# HVSUP_ISOL.net
KiCad netlist of a schematic drawn in Altium Designer
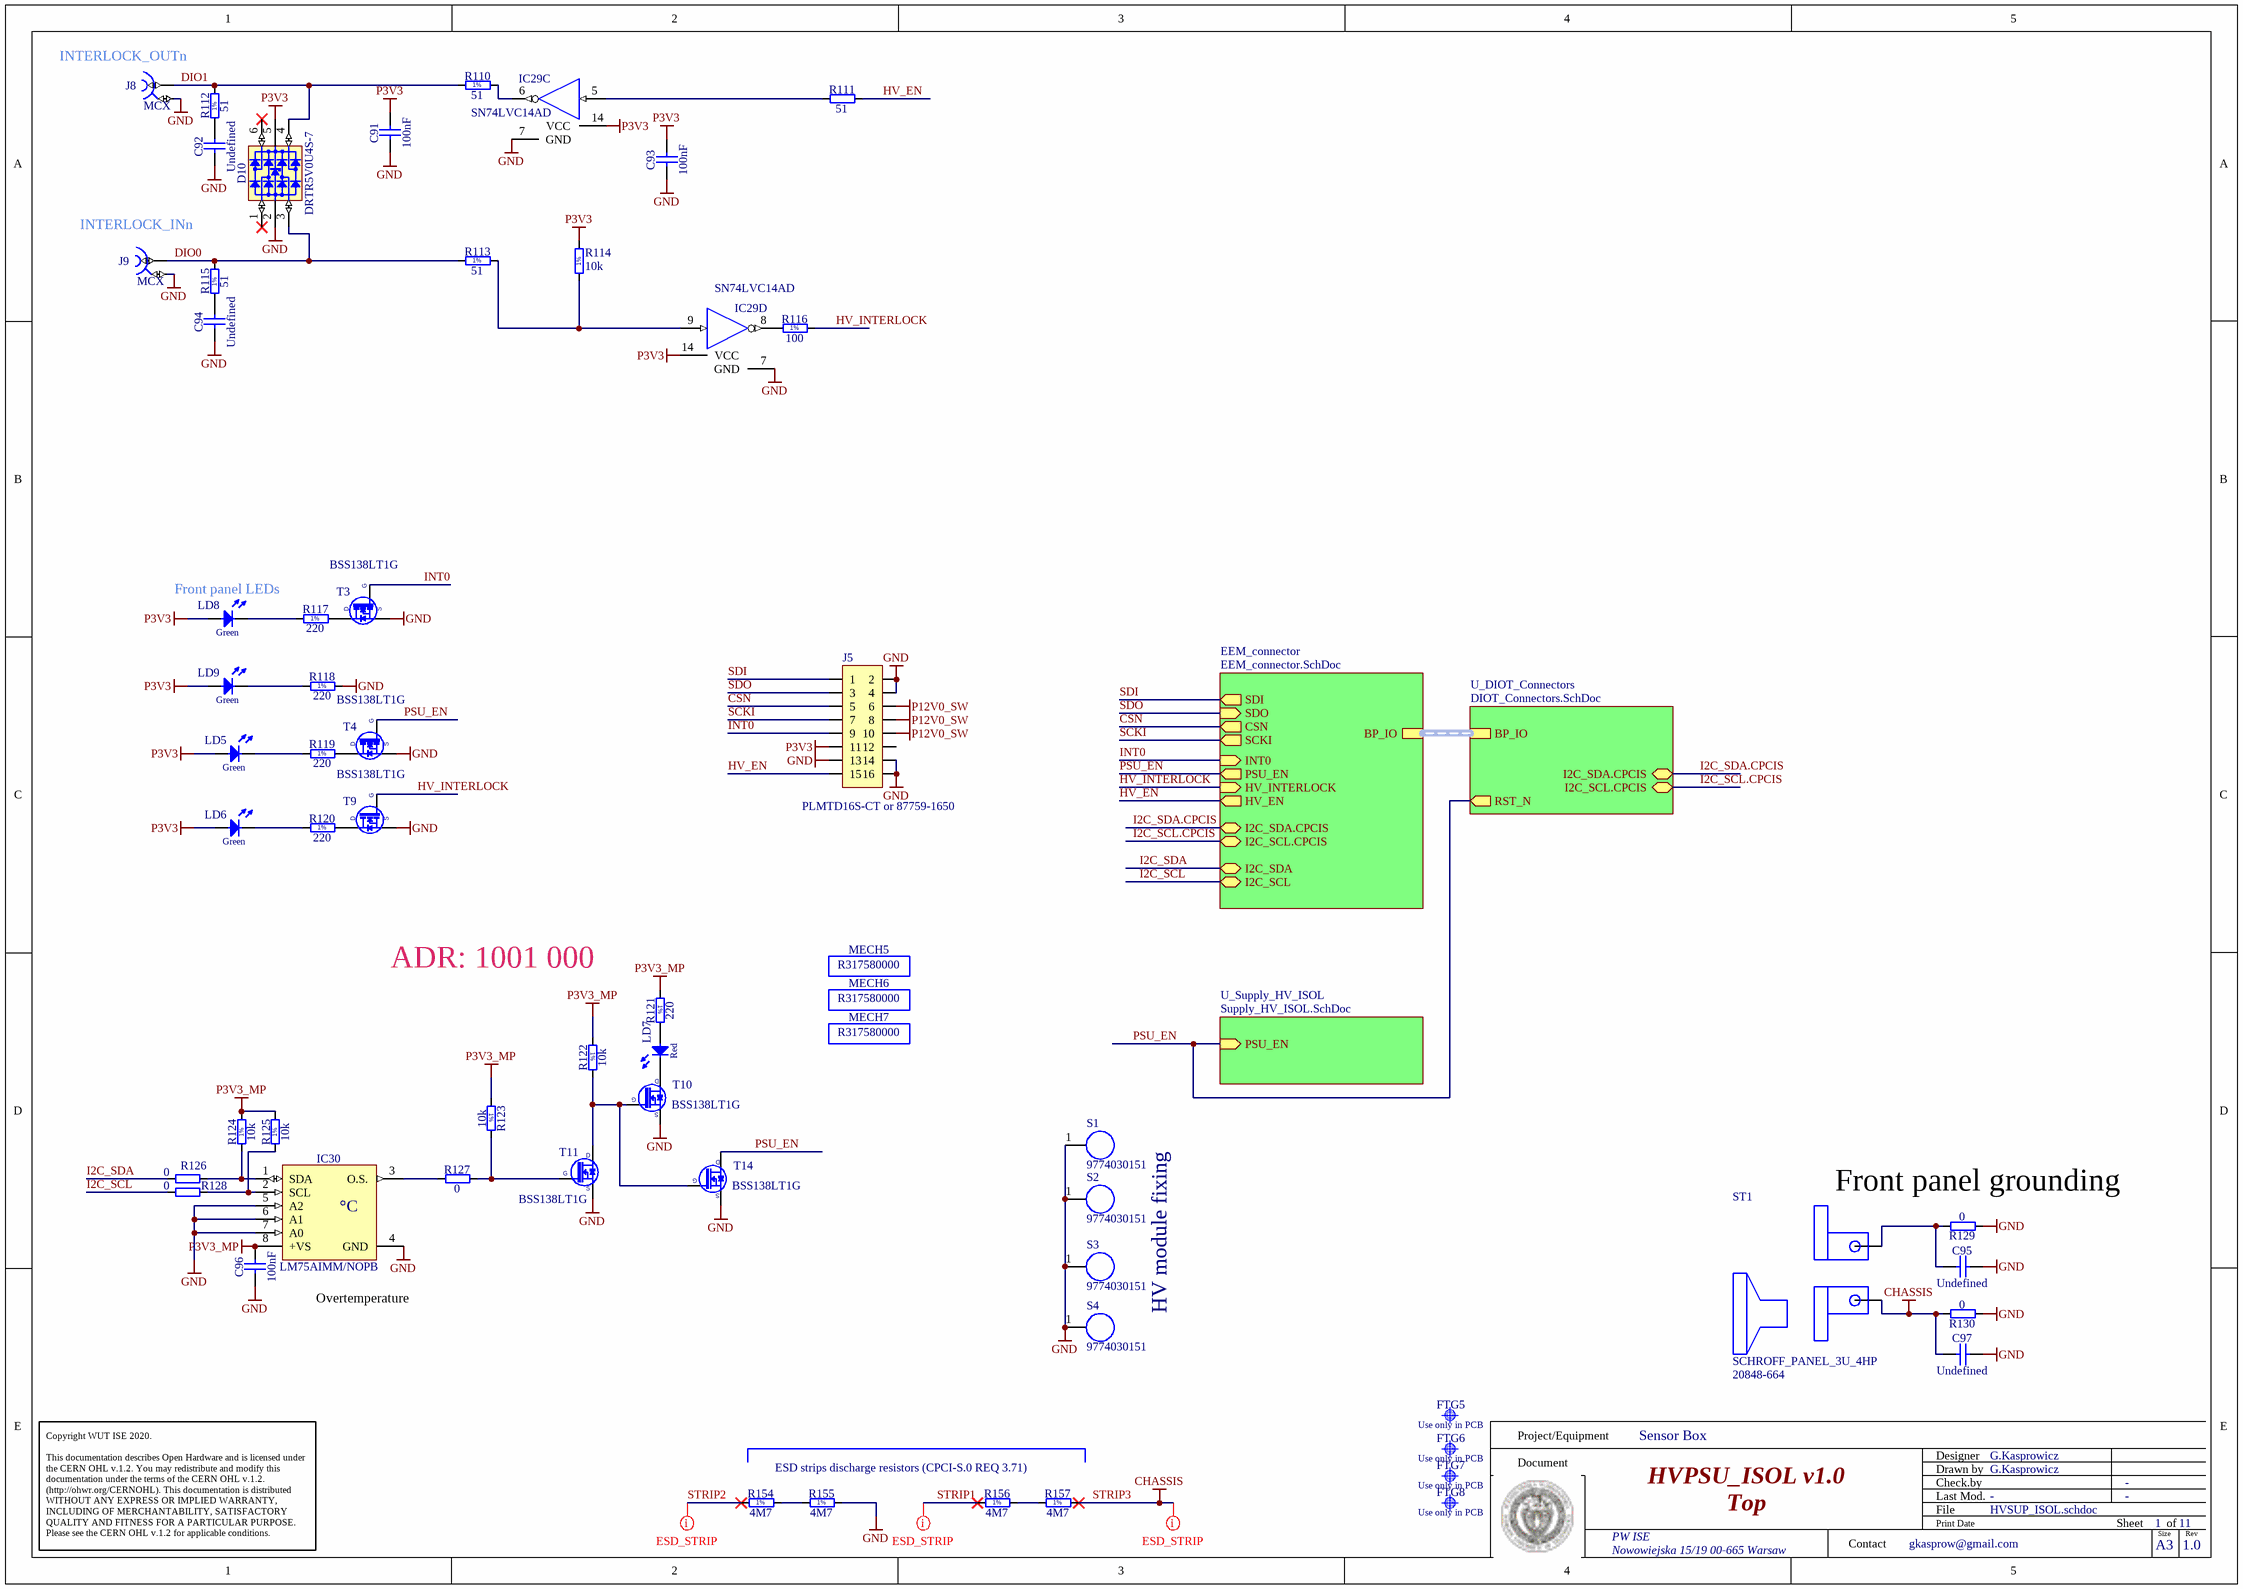
[diagram p0: HVSUP_ISOL.schdoc]

(export (version "E")
  (design (tool "Eeschema 10.0.6"))
  (components
    (comp (ref "C91")
      (value "100nF")
      (footprint "CAPC1005X55N")
      (description "Non-polarised capacitor")
      (fields
        (field (name "PART NUMBER") "CC0402_100NF_16V_10%_X7R")
        (field (name "VOLTAGE") "16V")
        (field (name "AUTHOR") "CERN DEM JLC")
      )
      (libsource (lib "Capacitors") (part "Capacitor - non polarized"))
    )
    (comp (ref "C92")
      (value "Undefined")
      (footprint "CAPC1608X90N")
      (description "Non-polarised capacitor")
      (fields (field (name "PART NUMBER") "CC0603_NO-VALUE") (field (name "AUTHOR") "CERN DEM MR"))
      (libsource (lib "Capacitors") (part "Capacitor - non polarized"))
    )
    (comp (ref "C93")
      (value "100nF")
      (footprint "CAPC1005X55N")
      (description "Non-polarised capacitor")
      (fields
        (field (name "PART NUMBER") "CC0402_100NF_16V_10%_X7R")
        (field (name "VOLTAGE") "16V")
        (field (name "AUTHOR") "CERN DEM JLC")
      )
      (libsource (lib "Capacitors") (part "Capacitor - non polarized"))
    )
    (comp (ref "C94")
      (value "Undefined")
      (footprint "CAPC1608X90N")
      (description "Non-polarised capacitor")
      (fields (field (name "PART NUMBER") "CC0603_NO-VALUE") (field (name "AUTHOR") "CERN DEM MR"))
      (libsource (lib "Capacitors") (part "Capacitor - non polarized"))
    )
    (comp (ref "C95")
      (value "Undefined")
      (footprint "CAPC2012X135N")
      (description "Non-polarised capacitor")
      (fields (field (name "PART NUMBER") "CC0805_NO-VALUE") (field (name "AUTHOR") "CERN DEM JLC"))
      (libsource (lib "Capacitors") (part "Capacitor - non polarized"))
    )
    (comp (ref "C96")
      (value "100nF")
      (footprint "CAPC1005X55N")
      (description "Non-polarised capacitor")
      (fields
        (field (name "PART NUMBER") "CC0402_100NF_16V_10%_X5R")
        (field (name "VOLTAGE") "16V")
        (field (name "AUTHOR") "CERN DEM JLC")
      )
      (libsource (lib "Capacitors") (part "Capacitor - non polarized"))
    )
    (comp (ref "C97")
      (value "Undefined")
      (footprint "CAPC2012X135N")
      (description "Non-polarised capacitor")
      (fields (field (name "PART NUMBER") "CC0805_NO-VALUE") (field (name "AUTHOR") "CERN DEM JLC"))
      (libsource (lib "Capacitors") (part "Capacitor - non polarized"))
    )
    (comp (ref "D10")
      (value "DRTR5V0U4S-7")
      (footprint "SOT65P210X110-6N")
      (description "Integrated Quad Ultra-Low Capacitance ESD Protection")
      (fields (field (name "MANUFACTURER") "DIODES") (field (name "AUTHOR") "GK"))
      (libsource (lib "Diodes") (part "D_TVS_DRTR5V0U4S-7"))
    )
    (comp (ref "FTG5")
      (value "Use only in PCB")
      (footprint "FIDUCIAL_TOP_C100-200")
      (description "Fiducial Target")
      (fields (field (name "PART NUMBER") "FIDUCIAL_TARGET_C100-200") (field (name "AUTHOR") "CERN DEM JLC"))
      (libsource (lib "Eletro-mechanical") (part "Fiducial Target"))
    )
    (comp (ref "FTG6")
      (value "Use only in PCB")
      (footprint "FIDUCIAL_TOP_S100-200")
      (description "Fiducial Target")
      (fields (field (name "PART NUMBER") "FIDUCIAL_TARGET_S100-200") (field (name "AUTHOR") "CERN DEM JLC"))
      (libsource (lib "Eletro-mechanical") (part "Fiducial Target"))
    )
    (comp (ref "FTG7")
      (value "Use only in PCB")
      (footprint "FIDUCIAL_TOP_S100-200")
      (description "Fiducial Target")
      (fields (field (name "PART NUMBER") "FIDUCIAL_TARGET_S100-200") (field (name "AUTHOR") "CERN DEM JLC"))
      (libsource (lib "Eletro-mechanical") (part "Fiducial Target"))
    )
    (comp (ref "FTG8")
      (value "Use only in PCB")
      (footprint "FIDUCIAL_TOP_S100-200")
      (description "Fiducial Target")
      (fields (field (name "PART NUMBER") "FIDUCIAL_TARGET_S100-200") (field (name "AUTHOR") "CERN DEM JLC"))
      (libsource (lib "Eletro-mechanical") (part "Fiducial Target"))
    )
    (comp (ref "IC29")
      (value "SN74LVC14AD")
      (footprint "SOIC127P600X175-14N")
      (description "Hex Schmitt-Trigger Inverter")
      (fields (field (name "MANUFACTURER") "TEXAS INSTRUMENTS") (field (name "AUTHOR") "CERN DEM JMW"))
      (libsource (lib "ICs And Semiconductors") (part "7414"))
    )
    (comp (ref "IC30")
      (value "LM75AIMM/NOPB")
      (footprint "SOP65P490X109-8N")
      (description "Digital Temperature Sensor and Thermal Watchdog with Two-Wire Interface")
      (fields (field (name "MANUFACTURER") "TEXAS INSTRUMENTS") (field (name "AUTHOR") "CERN DEM JLC"))
      (libsource (lib "ICs And Semiconductors") (part "LM75"))
    )
    (comp (ref "J5")
      (value "PLMTD16S-CT or 87759-1650")
      (footprint "87759-1650")
      (description "2mm  dual row rheader (Maritex)")
      (fields (field (name "MANUFACTURER") "Molex") (field (name "MANUFACTURER PART NUMBER") "87759-1650"))
      (libsource (lib "LIBRARY_SCH") (part "CON_2x8 2mm male"))
    )
    (comp (ref "J8")
      (value "MCX")
      (footprint "AMPHENOL_919-383J-51A")
      (fields
        (field (name "PART NUMBER") "AMPHENOL_919-383J-51A")
        (field (name "MANUFACTURER") "AMPHENOL")
        (field (name "MANUFACTURER PART NUMBER") "919-383J-51A")
        (field (name "AUTHOR") "CERN DEM BC")
      )
      (libsource (lib "Connectors") (part "Coax_1Female_1Shield"))
    )
    (comp (ref "J9")
      (value "MCX")
      (footprint "AMPHENOL_919-383J-51A")
      (fields
        (field (name "PART NUMBER") "AMPHENOL_919-383J-51A")
        (field (name "MANUFACTURER") "AMPHENOL")
        (field (name "MANUFACTURER PART NUMBER") "919-383J-51A")
        (field (name "AUTHOR") "CERN DEM BC")
      )
      (libsource (lib "Connectors") (part "Coax_1Female_1Shield"))
    )
    (comp (ref "LD5")
      (value "Green")
      (footprint "LED_DIALIGHT_555-230")
      (description "LED Green 1C 2A")
      (fields
        (field (name "PART NUMBER") "LED_DIALIGHT_555-2301F")
        (field (name "MANUFACTURER") "DIALIGHT")
        (field (name "AUTHOR") "CERN DEM JMW")
      )
      (libsource (lib "ICs And Semiconductors") (part "LED Green 1C 2A"))
    )
    (comp (ref "LD6")
      (value "Green")
      (footprint "LED_DIALIGHT_555-230")
      (description "LED Green 1C 2A")
      (fields
        (field (name "PART NUMBER") "LED_DIALIGHT_555-2301F")
        (field (name "MANUFACTURER") "DIALIGHT")
        (field (name "AUTHOR") "CERN DEM JMW")
      )
      (libsource (lib "ICs And Semiconductors") (part "LED Green 1C 2A"))
    )
    (comp (ref "LD7")
      (value "Red")
      (footprint "LED_DIALIGHT_555-200")
      (description "LED Red 1C 2A")
      (fields
        (field (name "PART NUMBER") "LED_DIALIGHT_555-2001F")
        (field (name "MANUFACTURER") "DIALIGHT")
        (field (name "AUTHOR") "CERN DEM JMW")
      )
      (libsource (lib "ICs And Semiconductors") (part "LED Red 1C 2A"))
    )
    (comp (ref "LD8")
      (value "Green")
      (footprint "LED_DIALIGHT_555-230")
      (description "LED Green 1C 2A")
      (fields
        (field (name "PART NUMBER") "LED_DIALIGHT_555-2301F")
        (field (name "MANUFACTURER") "DIALIGHT")
        (field (name "AUTHOR") "CERN DEM JMW")
      )
      (libsource (lib "ICs And Semiconductors") (part "LED Green 1C 2A"))
    )
    (comp (ref "LD9")
      (value "Green")
      (footprint "LED_DIALIGHT_555-230")
      (description "LED Green 1C 2A")
      (fields
        (field (name "PART NUMBER") "LED_DIALIGHT_555-2301F")
        (field (name "MANUFACTURER") "DIALIGHT")
        (field (name "AUTHOR") "CERN DEM JMW")
      )
      (libsource (lib "ICs And Semiconductors") (part "LED Green 1C 2A"))
    )
    (comp (ref "MECH5")
      (value "R317580000")
      (footprint "GENERIC_MECH")
      (description "SHV connector")
      (fields (field (name "MANUFACTURER") "Radiall") (field (name "AUTHOR") "GK"))
      (libsource (lib "Mechanical") (part "Generic_mechanical"))
    )
    (comp (ref "MECH6")
      (value "R317580000")
      (footprint "GENERIC_MECH")
      (description "SHV connector")
      (fields (field (name "MANUFACTURER") "Radiall") (field (name "AUTHOR") "GK"))
      (libsource (lib "Mechanical") (part "Generic_mechanical"))
    )
    (comp (ref "MECH7")
      (value "R317580000")
      (footprint "GENERIC_MECH")
      (description "SHV connector")
      (fields (field (name "MANUFACTURER") "Radiall") (field (name "AUTHOR") "GK"))
      (libsource (lib "Mechanical") (part "Generic_mechanical"))
    )
    (comp (ref "R110")
      (value "51")
      (footprint "RESC1005X40N")
      (description "Resistor - 1%")
      (fields
        (field (name "PART NUMBER") "R0402_51R_1%_0.0625W_100PPM")
        (field (name "POWER") "0.0625W")
        (field (name "AUTHOR") "CERN DEM JLC")
      )
      (libsource (lib "Resistors") (part "Resistor - 1%"))
    )
    (comp (ref "R111")
      (value "51")
      (footprint "RESC1005X40N")
      (description "Resistor - 1%")
      (fields
        (field (name "PART NUMBER") "R0402_51R_1%_0.0625W_100PPM")
        (field (name "POWER") "0.0625W")
        (field (name "AUTHOR") "CERN DEM JLC")
      )
      (libsource (lib "Resistors") (part "Resistor - 1%"))
    )
    (comp (ref "R112")
      (value "51")
      (footprint "RESC1005X40N")
      (description "Resistor - 1%")
      (fields
        (field (name "PART NUMBER") "R0402_51R_1%_0.0625W_100PPM")
        (field (name "POWER") "0.0625W")
        (field (name "AUTHOR") "CERN DEM JLC")
      )
      (libsource (lib "Resistors") (part "Resistor - 1%"))
    )
    (comp (ref "R113")
      (value "51")
      (footprint "RESC1005X40N")
      (description "Resistor - 1%")
      (fields
        (field (name "PART NUMBER") "R0402_51R_1%_0.0625W_100PPM")
        (field (name "POWER") "0.0625W")
        (field (name "AUTHOR") "CERN DEM JLC")
      )
      (libsource (lib "Resistors") (part "Resistor - 1%"))
    )
    (comp (ref "R114")
      (value "10k")
      (footprint "RESC1005X40N")
      (description "Resistor - 1%")
      (fields
        (field (name "PART NUMBER") "R0402_10K_1%_0.0625W_100PPM")
        (field (name "POWER") "0.0625W")
        (field (name "AUTHOR") "CERN DEM JLC")
      )
      (libsource (lib "Resistors") (part "Resistor - 1%"))
    )
    (comp (ref "R115")
      (value "51")
      (footprint "RESC1005X40N")
      (description "Resistor - 1%")
      (fields
        (field (name "PART NUMBER") "R0402_51R_1%_0.0625W_100PPM")
        (field (name "POWER") "0.0625W")
        (field (name "AUTHOR") "CERN DEM JLC")
      )
      (libsource (lib "Resistors") (part "Resistor - 1%"))
    )
    (comp (ref "R116")
      (value "100")
      (footprint "RESC1005X40N")
      (description "Resistor - 1%")
      (fields
        (field (name "PART NUMBER") "R0402_100R_1%_0.0625W_100PPM")
        (field (name "POWER") "0.0625W")
        (field (name "AUTHOR") "CERN DEM JLC")
      )
      (libsource (lib "Resistors") (part "Resistor - 1%"))
    )
    (comp (ref "R117")
      (value "220")
      (footprint "RESC1608X55N")
      (description "Resistor - 1%")
      (fields
        (field (name "PART NUMBER") "R0603_220R_1%_0.1W_100PPM")
        (field (name "POWER") "0.1W")
        (field (name "AUTHOR") "CERN DEM JLC")
      )
      (libsource (lib "Resistors") (part "Resistor - 1%"))
    )
    (comp (ref "R118")
      (value "220")
      (footprint "RESC1608X55N")
      (description "Resistor - 1%")
      (fields
        (field (name "PART NUMBER") "R0603_220R_1%_0.1W_100PPM")
        (field (name "POWER") "0.1W")
        (field (name "AUTHOR") "CERN DEM JLC")
      )
      (libsource (lib "Resistors") (part "Resistor - 1%"))
    )
    (comp (ref "R119")
      (value "220")
      (footprint "RESC1608X55N")
      (description "Resistor - 1%")
      (fields
        (field (name "PART NUMBER") "R0603_220R_1%_0.1W_100PPM")
        (field (name "POWER") "0.1W")
        (field (name "AUTHOR") "CERN DEM JLC")
      )
      (libsource (lib "Resistors") (part "Resistor - 1%"))
    )
    (comp (ref "R120")
      (value "220")
      (footprint "RESC1608X55N")
      (description "Resistor - 1%")
      (fields
        (field (name "PART NUMBER") "R0603_220R_1%_0.1W_100PPM")
        (field (name "POWER") "0.1W")
        (field (name "AUTHOR") "CERN DEM JLC")
      )
      (libsource (lib "Resistors") (part "Resistor - 1%"))
    )
    (comp (ref "R121")
      (value "220")
      (footprint "RESC1608X55N")
      (description "Resistor - 1%")
      (fields
        (field (name "PART NUMBER") "R0603_220R_1%_0.1W_100PPM")
        (field (name "POWER") "0.1W")
        (field (name "AUTHOR") "CERN DEM JLC")
      )
      (libsource (lib "Resistors") (part "Resistor - 1%"))
    )
    (comp (ref "R122")
      (value "10k")
      (footprint "RESC1005X40N")
      (description "Resistor - 1%")
      (fields
        (field (name "PART NUMBER") "R0402_10K_1%_0.0625W_100PPM")
        (field (name "POWER") "0.0625W")
        (field (name "AUTHOR") "CERN DEM JLC")
      )
      (libsource (lib "Resistors") (part "Resistor - 1%"))
    )
    (comp (ref "R123")
      (value "10k")
      (footprint "RESC1005X40N")
      (description "Resistor - 1%")
      (fields
        (field (name "PART NUMBER") "R0402_10K_1%_0.0625W_100PPM")
        (field (name "POWER") "0.0625W")
        (field (name "AUTHOR") "CERN DEM JLC")
      )
      (libsource (lib "Resistors") (part "Resistor - 1%"))
    )
    (comp (ref "R124")
      (value "10k")
      (footprint "RESC1005X40N")
      (description "Resistor - 1%")
      (fields
        (field (name "PART NUMBER") "R0402_10K_1%_0.0625W_100PPM")
        (field (name "POWER") "0.0625W")
        (field (name "AUTHOR") "CERN DEM JLC")
      )
      (libsource (lib "Resistors") (part "Resistor - 1%"))
    )
    (comp (ref "R125")
      (value "10k")
      (footprint "RESC1005X40N")
      (description "Resistor - 1%")
      (fields
        (field (name "PART NUMBER") "R0402_10K_1%_0.0625W_100PPM")
        (field (name "POWER") "0.0625W")
        (field (name "AUTHOR") "CERN DEM JLC")
      )
      (libsource (lib "Resistors") (part "Resistor - 1%"))
    )
    (comp (ref "R126")
      (value "0")
      (footprint "RESC1005X40N")
      (description "Resistor")
      (fields
        (field (name "PART NUMBER") "R0402_0R_JUMPER")
        (field (name "MANUFACTURER") "GENERIC")
        (field (name "AUTHOR") "CERN DEM JLC")
      )
      (libsource (lib "Resistors") (part "Resistor"))
    )
    (comp (ref "R127")
      (value "0")
      (footprint "RESC1005X40N")
      (description "Resistor")
      (fields
        (field (name "PART NUMBER") "R0402_0R_JUMPER")
        (field (name "MANUFACTURER") "GENERIC")
        (field (name "AUTHOR") "CERN DEM JLC")
      )
      (libsource (lib "Resistors") (part "Resistor"))
    )
    (comp (ref "R128")
      (value "0")
      (footprint "RESC1005X40N")
      (description "Resistor")
      (fields
        (field (name "PART NUMBER") "R0402_0R_JUMPER")
        (field (name "MANUFACTURER") "GENERIC")
        (field (name "AUTHOR") "CERN DEM JLC")
      )
      (libsource (lib "Resistors") (part "Resistor"))
    )
    (comp (ref "R129")
      (value "0")
      (footprint "RESC1608X55N")
      (description "Resistor")
      (fields
        (field (name "PART NUMBER") "R0603_0R_JUMPER")
        (field (name "MANUFACTURER") "GENERIC")
        (field (name "AUTHOR") "CERN DEM JLC")
      )
      (libsource (lib "Resistors") (part "Resistor"))
    )
    (comp (ref "R130")
      (value "0")
      (footprint "RESC1608X55N")
      (description "Resistor")
      (fields
        (field (name "PART NUMBER") "R0603_0R_JUMPER")
        (field (name "MANUFACTURER") "GENERIC")
        (field (name "AUTHOR") "CERN DEM JLC")
      )
      (libsource (lib "Resistors") (part "Resistor"))
    )
    (comp (ref "R154")
      (value "4M7")
      (footprint "RESC2113X55N")
      (description "Resistor - 1%")
      (fields
        (field (name "PART NUMBER") "R0805_4M7_1%_0.125W_100PPM_VISHAY_CRCW e3")
        (field (name "POWER") "0.125W")
        (field (name "AUTHOR") "CERN DEM BR")
      )
      (libsource (lib "Resistors") (part "Resistor - 1%"))
    )
    (comp (ref "R155")
      (value "4M7")
      (footprint "RESC2113X55N")
      (description "Resistor - 1%")
      (fields
        (field (name "PART NUMBER") "R0805_4M7_1%_0.125W_100PPM_VISHAY_CRCW e3")
        (field (name "POWER") "0.125W")
        (field (name "AUTHOR") "CERN DEM BR")
      )
      (libsource (lib "Resistors") (part "Resistor - 1%"))
    )
    (comp (ref "R156")
      (value "4M7")
      (footprint "RESC2113X55N")
      (description "Resistor - 1%")
      (fields
        (field (name "PART NUMBER") "R0805_4M7_1%_0.125W_100PPM_VISHAY_CRCW e3")
        (field (name "POWER") "0.125W")
        (field (name "AUTHOR") "CERN DEM BR")
      )
      (libsource (lib "Resistors") (part "Resistor - 1%"))
    )
    (comp (ref "R157")
      (value "4M7")
      (footprint "RESC2113X55N")
      (description "Resistor - 1%")
      (fields
        (field (name "PART NUMBER") "R0805_4M7_1%_0.125W_100PPM_VISHAY_CRCW e3")
        (field (name "POWER") "0.125W")
        (field (name "AUTHOR") "CERN DEM BR")
      )
      (libsource (lib "Resistors") (part "Resistor - 1%"))
    )
    (comp (ref "S1")
      (value "9774030151")
      (footprint "9774030151")
      (description "WA-SMSI SMD Steel Spacer with internal Thread")
      (fields (field (name "MANUFACTURER") "Wurth Elektronik") (field (name "CREATED BY") "Baojun Chen"))
      (libsource (lib "Altium_SMSI_SMT_STEEL_SPACER_M2_5_THREAD_INTERNAL_rev15a") (part "WA-SMSI,  9774030151"))
    )
    (comp (ref "S2")
      (value "9774030151")
      (footprint "9774030151")
      (description "WA-SMSI SMD Steel Spacer with internal Thread")
      (fields (field (name "MANUFACTURER") "Wurth Elektronik") (field (name "CREATED BY") "Baojun Chen"))
      (libsource (lib "Altium_SMSI_SMT_STEEL_SPACER_M2_5_THREAD_INTERNAL_rev15a") (part "WA-SMSI,  9774030151"))
    )
    (comp (ref "S3")
      (value "9774030151")
      (footprint "9774030151")
      (description "WA-SMSI SMD Steel Spacer with internal Thread")
      (fields (field (name "MANUFACTURER") "Wurth Elektronik") (field (name "CREATED BY") "Baojun Chen"))
      (libsource (lib "Altium_SMSI_SMT_STEEL_SPACER_M2_5_THREAD_INTERNAL_rev15a") (part "WA-SMSI,  9774030151"))
    )
    (comp (ref "S4")
      (value "9774030151")
      (footprint "9774030151")
      (description "WA-SMSI SMD Steel Spacer with internal Thread")
      (fields (field (name "MANUFACTURER") "Wurth Elektronik") (field (name "CREATED BY") "Baojun Chen"))
      (libsource (lib "Altium_SMSI_SMT_STEEL_SPACER_M2_5_THREAD_INTERNAL_rev15a") (part "WA-SMSI,  9774030151"))
    )
    (comp (ref "ST1")
      (value "SCHROFF_PANEL_3U_4HP")
      (footprint "SCHROFF_PANEL_3HP_4U")
      (description "Schroff 3HP 4U EUROCARD Panel Kit")
      (fields
        (field (name "MANUFACTURER") "Schroff")
        (field (name "MANUFACTURER PART NUMBER") "20818-017")
        (field (name "MANUFACTURER PART NUMBER 2") "20848-664")
      )
      (libsource (lib "Mechanical") (part "SCHROFF_PANEL_3U_4HP"))
    )
    (comp (ref "T3")
      (value "BSS138LT1G")
      (footprint "SOT95P240X110-3N")
      (description "N-CHANNEL MOSFET WITH DIODE")
      (fields (field (name "MANUFACTURER") "ON SEMICONDUCTOR") (field (name "AUTHOR") "CERN DEM JLC"))
      (libsource (lib "ICs And Semiconductors") (part "N-MOSFET-D 1G 2S 3D"))
    )
    (comp (ref "T4")
      (value "BSS138LT1G")
      (footprint "SOT95P240X110-3N")
      (description "N-CHANNEL MOSFET WITH DIODE")
      (fields (field (name "MANUFACTURER") "ON SEMICONDUCTOR") (field (name "AUTHOR") "CERN DEM JLC"))
      (libsource (lib "ICs And Semiconductors") (part "N-MOSFET-D 1G 2S 3D"))
    )
    (comp (ref "T9")
      (value "BSS138LT1G")
      (footprint "SOT95P240X110-3N")
      (description "N-CHANNEL MOSFET WITH DIODE")
      (fields (field (name "MANUFACTURER") "ON SEMICONDUCTOR") (field (name "AUTHOR") "CERN DEM JLC"))
      (libsource (lib "ICs And Semiconductors") (part "N-MOSFET-D 1G 2S 3D"))
    )
    (comp (ref "T10")
      (value "BSS138LT1G")
      (footprint "SOT95P240X110-3N")
      (description "N-CHANNEL MOSFET WITH DIODE")
      (fields (field (name "MANUFACTURER") "ON SEMICONDUCTOR") (field (name "AUTHOR") "CERN DEM JLC"))
      (libsource (lib "") (part "N-MOSFET-D 1G 2S 3D_1"))
    )
    (comp (ref "T11")
      (value "BSS138LT1G")
      (footprint "SOT95P240X110-3N")
      (description "N-CHANNEL MOSFET WITH DIODE")
      (fields (field (name "MANUFACTURER") "ON SEMICONDUCTOR") (field (name "AUTHOR") "CERN DEM JLC"))
      (libsource (lib "") (part "N-MOSFET-D 1G 2S 3D_2"))
    )
    (comp (ref "T14")
      (value "BSS138LT1G")
      (footprint "SOT95P240X110-3N")
      (description "N-CHANNEL MOSFET WITH DIODE")
      (fields (field (name "MANUFACTURER") "ON SEMICONDUCTOR") (field (name "AUTHOR") "CERN DEM JLC"))
      (libsource (lib "") (part "N-MOSFET-D 1G 2S 3D_1"))
    )
  )
  (nets
    (net (code "2") (name "/CSN") (class "Default")
      (node (ref "J5") (pin "5") (pinfunction "5_5") (pintype "passive"))
    )
    (net (code "3") (name "/DIO0") (class "Default")
      (node (ref "D10") (pin "3") (pinfunction "I/O2_3") (pintype "bidirectional"))
      (node (ref "J9") (pin "1") (pinfunction "1_1") (pintype "bidirectional"))
      (node (ref "R113") (pin "1") (pinfunction "1_1") (pintype "passive"))
      (node (ref "R115") (pin "2") (pinfunction "2_2") (pintype "passive"))
    )
    (net (code "4") (name "/DIO1") (class "Default")
      (node (ref "D10") (pin "4") (pinfunction "I/O3_4") (pintype "bidirectional"))
      (node (ref "J8") (pin "1") (pinfunction "1_1") (pintype "bidirectional"))
      (node (ref "R110") (pin "1") (pinfunction "1_1") (pintype "passive"))
      (node (ref "R112") (pin "2") (pinfunction "2_2") (pintype "passive"))
    )
    (net (code "5") (name "/HV_EN") (class "Default")
      (node (ref "J5") (pin "15") (pinfunction "15_15") (pintype "passive"))
      (node (ref "R111") (pin "2") (pinfunction "2_2") (pintype "passive"))
    )
    (net (code "6") (name "/HV_INTERLOCK") (class "Default")
      (node (ref "R116") (pin "2") (pinfunction "2_2") (pintype "passive"))
      (node (ref "T9") (pin "1") (pinfunction "G_1") (pintype "passive"))
    )
    (net (code "7") (name "/I2C_SCL") (class "Default")
      (node (ref "R128") (pin "1") (pinfunction "1_1") (pintype "passive"))
    )
    (net (code "9") (name "/I2C_SDA") (class "Default")
      (node (ref "R126") (pin "1") (pinfunction "1_1") (pintype "passive"))
    )
    (net (code "11") (name "/INT0") (class "Default")
      (node (ref "J5") (pin "9") (pinfunction "9_9") (pintype "passive"))
      (node (ref "T3") (pin "1") (pinfunction "G_1") (pintype "passive"))
    )
    (net (code "12") (name "/PSU_EN") (class "Default")
      (node (ref "T14") (pin "3") (pinfunction "D_3") (pintype "passive"))
      (node (ref "T4") (pin "1") (pinfunction "G_1") (pintype "passive"))
    )
    (net (code "13") (name "/SCKI") (class "Default")
      (node (ref "J5") (pin "7") (pinfunction "7_7") (pintype "passive"))
    )
    (net (code "14") (name "/SDI") (class "Default")
      (node (ref "J5") (pin "1") (pinfunction "1_1") (pintype "passive"))
    )
    (net (code "15") (name "/SDO") (class "Default")
      (node (ref "J5") (pin "3") (pinfunction "3_3") (pintype "passive"))
    )
    (net (code "16") (name "/STRIP1") (class "Default")
      (node (ref "R156") (pin "1") (pinfunction "1_1") (pintype "passive+no_connect"))
    )
    (net (code "17") (name "/STRIP2") (class "Default")
      (node (ref "R154") (pin "1") (pinfunction "1_1") (pintype "passive+no_connect"))
    )
    (net (code "18") (name "CHASSIS") (class "Default")
      (node (ref "C97") (pin "1") (pinfunction "1_1") (pintype "passive"))
      (node (ref "R130") (pin "2") (pinfunction "2_2") (pintype "passive"))
      (node (ref "R157") (pin "2") (pinfunction "2_2") (pintype "passive"))
      (node (ref "ST1") (pin "0") (pinfunction "0_0") (pintype "passive"))
    )
    (net (code "19") (name "GND") (class "Default")
      (node (ref "C91") (pin "1") (pinfunction "1_1") (pintype "passive"))
      (node (ref "C92") (pin "1") (pinfunction "1_1") (pintype "passive"))
      (node (ref "C93") (pin "1") (pinfunction "1_1") (pintype "passive"))
      (node (ref "C94") (pin "1") (pinfunction "1_1") (pintype "passive"))
      (node (ref "C95") (pin "2") (pinfunction "2_2") (pintype "passive"))
      (node (ref "C96") (pin "1") (pinfunction "1_1") (pintype "passive"))
      (node (ref "C97") (pin "2") (pinfunction "2_2") (pintype "passive"))
      (node (ref "D10") (pin "2") (pinfunction "GND_2") (pintype "power_in"))
      (node (ref "IC29") (pin "7") (pinfunction "GND_7") (pintype "power_in"))
      (node (ref "IC30") (pin "4") (pinfunction "GND_4") (pintype "power_in"))
      (node (ref "IC30") (pin "5") (pinfunction "A2_5") (pintype "input"))
      (node (ref "IC30") (pin "6") (pinfunction "A1_6") (pintype "input"))
      (node (ref "IC30") (pin "7") (pinfunction "A0_7") (pintype "input"))
      (node (ref "J5") (pin "13") (pinfunction "13_13") (pintype "passive"))
      (node (ref "J5") (pin "14") (pinfunction "14_14") (pintype "passive"))
      (node (ref "J5") (pin "16") (pinfunction "16_16") (pintype "passive"))
      (node (ref "J5") (pin "2") (pinfunction "2_2") (pintype "passive"))
      (node (ref "J5") (pin "4") (pinfunction "4_4") (pintype "passive"))
      (node (ref "J8") (pin "2") (pinfunction "2_2") (pintype "bidirectional"))
      (node (ref "J9") (pin "2") (pinfunction "2_2") (pintype "bidirectional"))
      (node (ref "R118") (pin "2") (pinfunction "2_2") (pintype "passive"))
      (node (ref "R129") (pin "1") (pinfunction "1_1") (pintype "passive"))
      (node (ref "R130") (pin "1") (pinfunction "1_1") (pintype "passive"))
      (node (ref "R155") (pin "2") (pinfunction "2_2") (pintype "passive"))
      (node (ref "S1") (pin "1") (pinfunction "1_1") (pintype "passive"))
      (node (ref "S2") (pin "1") (pinfunction "1_1") (pintype "passive"))
      (node (ref "S3") (pin "1") (pinfunction "1_1") (pintype "passive"))
      (node (ref "S4") (pin "1") (pinfunction "1_1") (pintype "passive"))
      (node (ref "T10") (pin "2") (pinfunction "S_2") (pintype "passive"))
      (node (ref "T11") (pin "2") (pinfunction "S_2") (pintype "passive"))
      (node (ref "T14") (pin "2") (pinfunction "S_2") (pintype "passive"))
      (node (ref "T3") (pin "2") (pinfunction "S_2") (pintype "passive"))
      (node (ref "T4") (pin "2") (pinfunction "S_2") (pintype "passive"))
      (node (ref "T9") (pin "2") (pinfunction "S_2") (pintype "passive"))
    )
    (net (code "20") (name "Net-(C92-Pad2)") (class "Default")
      (node (ref "C92") (pin "2") (pinfunction "2_2") (pintype "passive"))
      (node (ref "R112") (pin "1") (pinfunction "1_1") (pintype "passive"))
    )
    (net (code "21") (name "Net-(C94-Pad2)") (class "Default")
      (node (ref "C94") (pin "2") (pinfunction "2_2") (pintype "passive"))
      (node (ref "R115") (pin "1") (pinfunction "1_1") (pintype "passive"))
    )
    (net (code "22") (name "Net-(C95-Pad1)") (class "Default")
      (node (ref "C95") (pin "1") (pinfunction "1_1") (pintype "passive"))
      (node (ref "R129") (pin "2") (pinfunction "2_2") (pintype "passive"))
      (node (ref "ST1") (pin "1") (pinfunction "1_1") (pintype "passive"))
    )
    (net (code "23") (name "Net-(IC29C-IN)") (class "Default")
      (node (ref "IC29") (pin "5") (pinfunction "IN_5") (pintype "input"))
      (node (ref "R111") (pin "1") (pinfunction "1_1") (pintype "passive"))
    )
    (net (code "24") (name "Net-(IC29C-OUT)") (class "Default")
      (node (ref "IC29") (pin "6") (pinfunction "OUT_6") (pintype "output"))
      (node (ref "R110") (pin "2") (pinfunction "2_2") (pintype "passive"))
    )
    (net (code "25") (name "Net-(IC29D-IN)") (class "Default")
      (node (ref "IC29") (pin "9") (pinfunction "IN_9") (pintype "input"))
      (node (ref "R113") (pin "2") (pinfunction "2_2") (pintype "passive"))
      (node (ref "R114") (pin "1") (pinfunction "1_1") (pintype "passive"))
    )
    (net (code "26") (name "Net-(IC29D-OUT)") (class "Default")
      (node (ref "IC29") (pin "8") (pinfunction "OUT_8") (pintype "output"))
      (node (ref "R116") (pin "1") (pinfunction "1_1") (pintype "passive"))
    )
    (net (code "27") (name "Net-(IC30-O.S.)") (class "Default")
      (node (ref "IC30") (pin "3") (pinfunction "O.S._3") (pintype "output"))
      (node (ref "R127") (pin "1") (pinfunction "1_1") (pintype "passive"))
    )
    (net (code "28") (name "Net-(IC30-SCL)") (class "Default")
      (node (ref "IC30") (pin "2") (pinfunction "SCL_2") (pintype "input"))
      (node (ref "R125") (pin "1") (pinfunction "1_1") (pintype "passive"))
      (node (ref "R128") (pin "2") (pinfunction "2_2") (pintype "passive"))
    )
    (net (code "29") (name "Net-(IC30-SDA)") (class "Default")
      (node (ref "IC30") (pin "1") (pinfunction "SDA_1") (pintype "bidirectional"))
      (node (ref "R124") (pin "1") (pinfunction "1_1") (pintype "passive"))
      (node (ref "R126") (pin "2") (pinfunction "2_2") (pintype "passive"))
    )
    (net (code "30") (name "Net-(LD5-C)") (class "Default")
      (node (ref "LD5") (pin "1") (pinfunction "C_1") (pintype "passive"))
      (node (ref "R119") (pin "1") (pinfunction "1_1") (pintype "passive"))
    )
    (net (code "31") (name "Net-(LD6-C)") (class "Default")
      (node (ref "LD6") (pin "1") (pinfunction "C_1") (pintype "passive"))
      (node (ref "R120") (pin "1") (pinfunction "1_1") (pintype "passive"))
    )
    (net (code "32") (name "Net-(LD7-A)") (class "Default")
      (node (ref "LD7") (pin "2") (pinfunction "A_2") (pintype "passive"))
      (node (ref "R121") (pin "2") (pinfunction "2_2") (pintype "passive"))
    )
    (net (code "33") (name "Net-(LD7-C)") (class "Default")
      (node (ref "LD7") (pin "1") (pinfunction "C_1") (pintype "passive"))
      (node (ref "T10") (pin "3") (pinfunction "D_3") (pintype "passive"))
    )
    (net (code "34") (name "Net-(LD8-C)") (class "Default")
      (node (ref "LD8") (pin "1") (pinfunction "C_1") (pintype "passive"))
      (node (ref "R117") (pin "1") (pinfunction "1_1") (pintype "passive"))
    )
    (net (code "35") (name "Net-(LD9-C)") (class "Default")
      (node (ref "LD9") (pin "1") (pinfunction "C_1") (pintype "passive"))
      (node (ref "R118") (pin "1") (pinfunction "1_1") (pintype "passive"))
    )
    (net (code "36") (name "Net-(R154-Pad2)") (class "Default")
      (node (ref "R154") (pin "2") (pinfunction "2_2") (pintype "passive"))
      (node (ref "R155") (pin "1") (pinfunction "1_1") (pintype "passive"))
    )
    (net (code "37") (name "Net-(R156-Pad2)") (class "Default")
      (node (ref "R156") (pin "2") (pinfunction "2_2") (pintype "passive"))
      (node (ref "R157") (pin "1") (pinfunction "1_1") (pintype "passive"))
    )
    (net (code "38") (name "Net-(T3-D)") (class "Default")
      (node (ref "R117") (pin "2") (pinfunction "2_2") (pintype "passive"))
      (node (ref "T3") (pin "3") (pinfunction "D_3") (pintype "passive"))
    )
    (net (code "39") (name "Net-(T4-D)") (class "Default")
      (node (ref "R119") (pin "2") (pinfunction "2_2") (pintype "passive"))
      (node (ref "T4") (pin "3") (pinfunction "D_3") (pintype "passive"))
    )
    (net (code "40") (name "Net-(T9-D)") (class "Default")
      (node (ref "R120") (pin "2") (pinfunction "2_2") (pintype "passive"))
      (node (ref "T9") (pin "3") (pinfunction "D_3") (pintype "passive"))
    )
    (net (code "41") (name "Net-(T10-G)") (class "Default")
      (node (ref "R122") (pin "2") (pinfunction "2_2") (pintype "passive"))
      (node (ref "T10") (pin "1") (pinfunction "G_1") (pintype "passive"))
      (node (ref "T11") (pin "3") (pinfunction "D_3") (pintype "passive"))
      (node (ref "T14") (pin "1") (pinfunction "G_1") (pintype "passive"))
    )
    (net (code "42") (name "Net-(T11-G)") (class "Default")
      (node (ref "R123") (pin "2") (pinfunction "2_2") (pintype "passive"))
      (node (ref "R127") (pin "2") (pinfunction "2_2") (pintype "passive"))
      (node (ref "T11") (pin "1") (pinfunction "G_1") (pintype "passive"))
    )
    (net (code "43") (name "P3V3") (class "Default")
      (node (ref "C91") (pin "2") (pinfunction "2_2") (pintype "passive"))
      (node (ref "C93") (pin "2") (pinfunction "2_2") (pintype "passive"))
      (node (ref "D10") (pin "5") (pinfunction "VBUS_5") (pintype "power_in"))
      (node (ref "IC29") (pin "14") (pinfunction "VCC_14") (pintype "power_in"))
      (node (ref "J5") (pin "11") (pinfunction "11_11") (pintype "passive"))
      (node (ref "LD5") (pin "2") (pinfunction "A_2") (pintype "passive"))
      (node (ref "LD6") (pin "2") (pinfunction "A_2") (pintype "passive"))
      (node (ref "LD8") (pin "2") (pinfunction "A_2") (pintype "passive"))
      (node (ref "LD9") (pin "2") (pinfunction "A_2") (pintype "passive"))
      (node (ref "R114") (pin "2") (pinfunction "2_2") (pintype "passive"))
    )
    (net (code "44") (name "P3V3_MP") (class "Default")
      (node (ref "C96") (pin "2") (pinfunction "2_2") (pintype "passive"))
      (node (ref "IC30") (pin "8") (pinfunction "+VS_8") (pintype "power_in"))
      (node (ref "R121") (pin "1") (pinfunction "1_1") (pintype "passive"))
      (node (ref "R122") (pin "1") (pinfunction "1_1") (pintype "passive"))
      (node (ref "R123") (pin "1") (pinfunction "1_1") (pintype "passive"))
      (node (ref "R124") (pin "2") (pinfunction "2_2") (pintype "passive"))
      (node (ref "R125") (pin "2") (pinfunction "2_2") (pintype "passive"))
    )
    (net (code "45") (name "P12V0_SW") (class "Default")
      (node (ref "J5") (pin "10") (pinfunction "10_10") (pintype "passive"))
      (node (ref "J5") (pin "6") (pinfunction "6_6") (pintype "passive"))
      (node (ref "J5") (pin "8") (pinfunction "8_8") (pintype "passive"))
    )
    (net (code "46") (name "unconnected-(D10-I{slash}O1-Pad1)") (class "Default")
      (node (ref "D10") (pin "1") (pinfunction "I/O1_1") (pintype "bidirectional+no_connect"))
    )
    (net (code "47") (name "unconnected-(D10-I{slash}O4-Pad6)") (class "Default")
      (node (ref "D10") (pin "6") (pinfunction "I/O4_6") (pintype "bidirectional+no_connect"))
    )
    (net (code "48") (name "unconnected-(J5-Pad12)") (class "Default")
      (node (ref "J5") (pin "12") (pinfunction "12_12") (pintype "passive"))
    )
  )
)
